# project_buran_schematic.net
KiCad netlist of a schematic drawn in Altium Designer
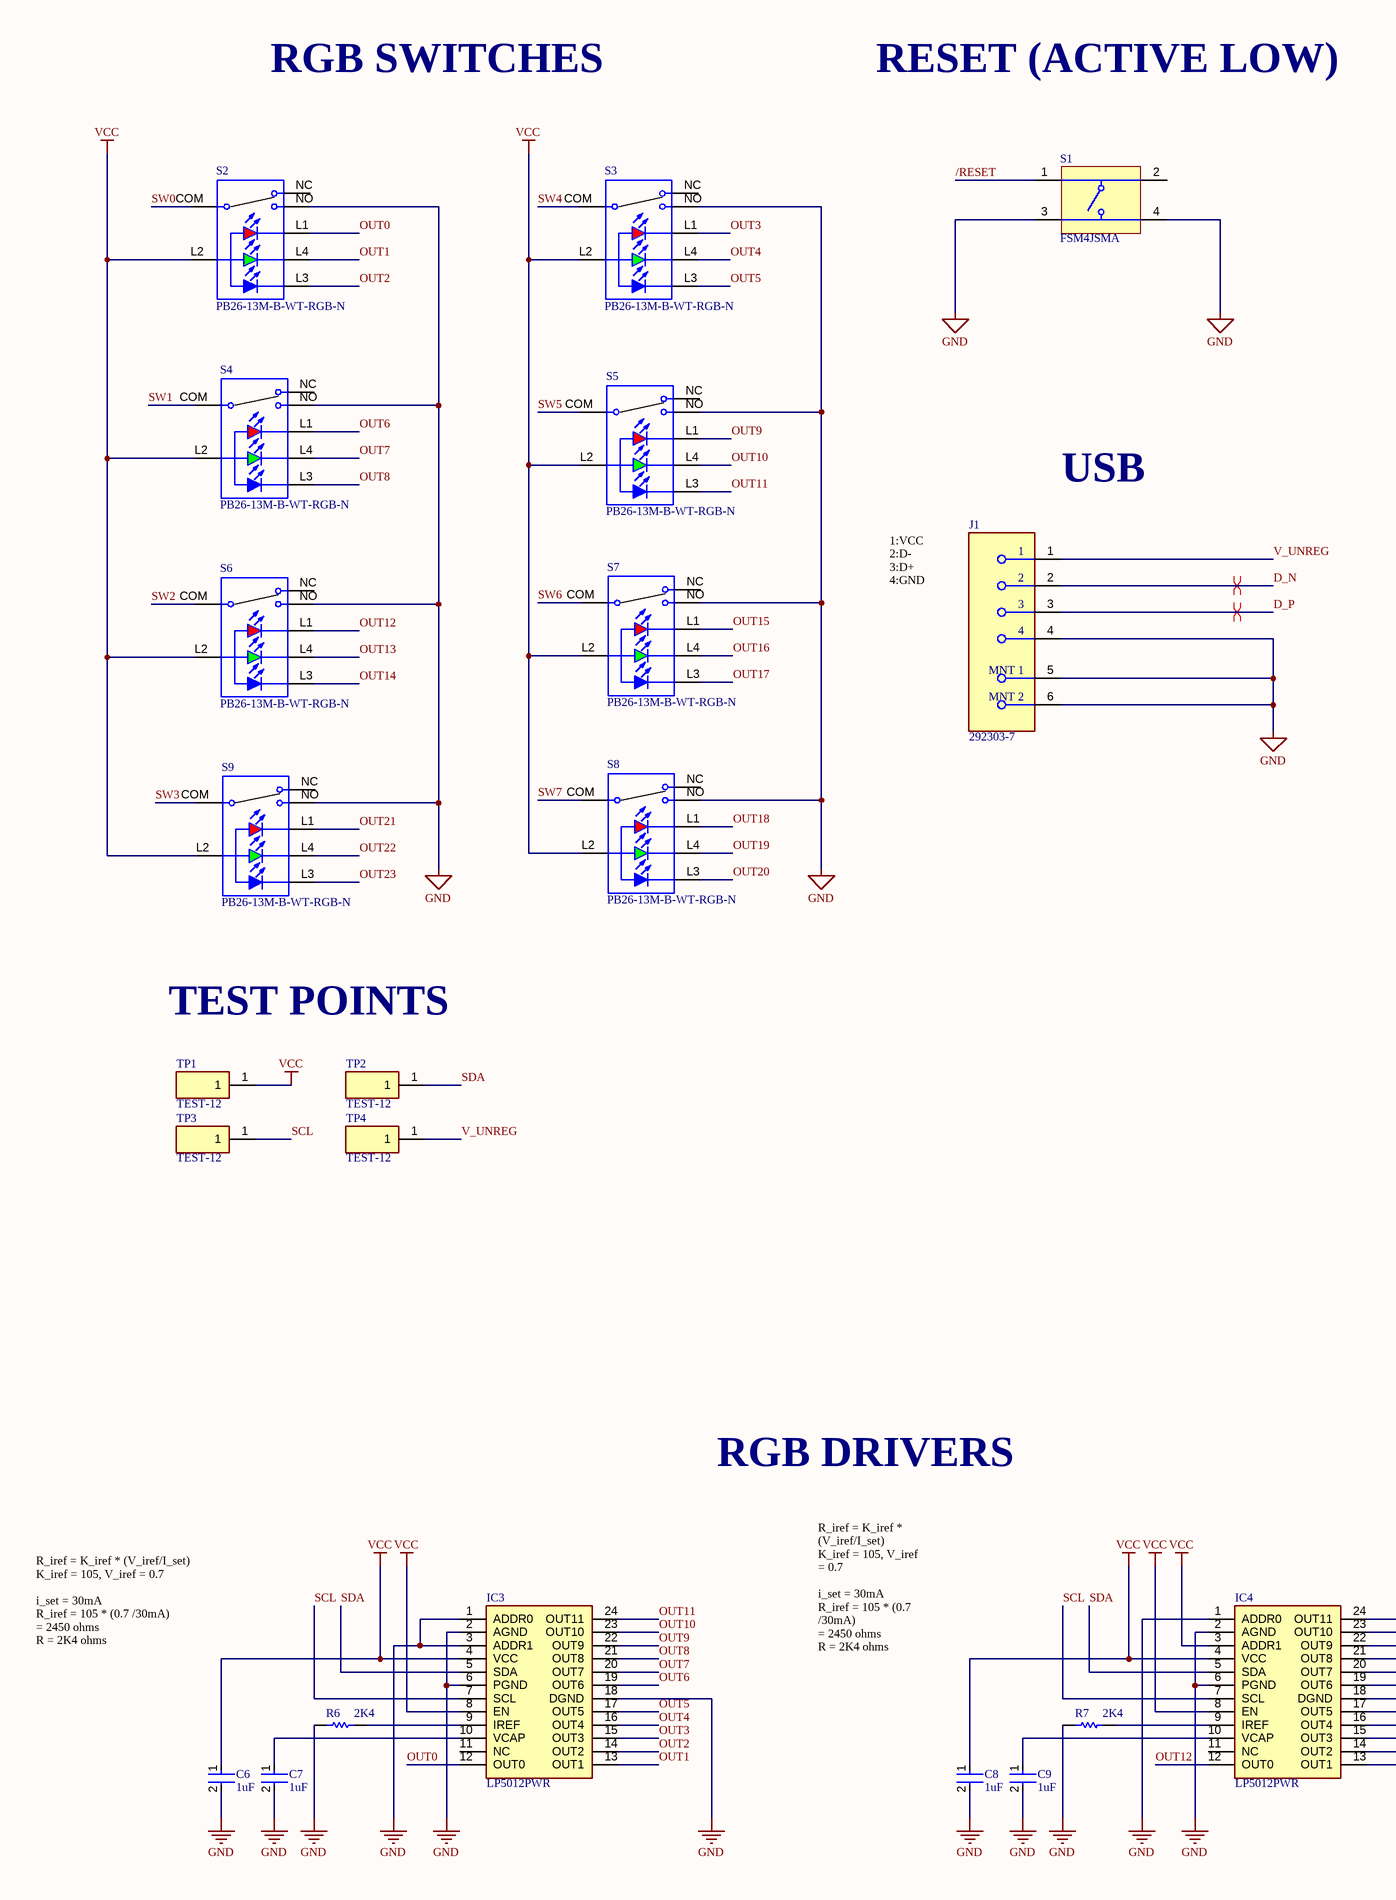
[diagram p0: project_buran_schematic.SchDoc, left]
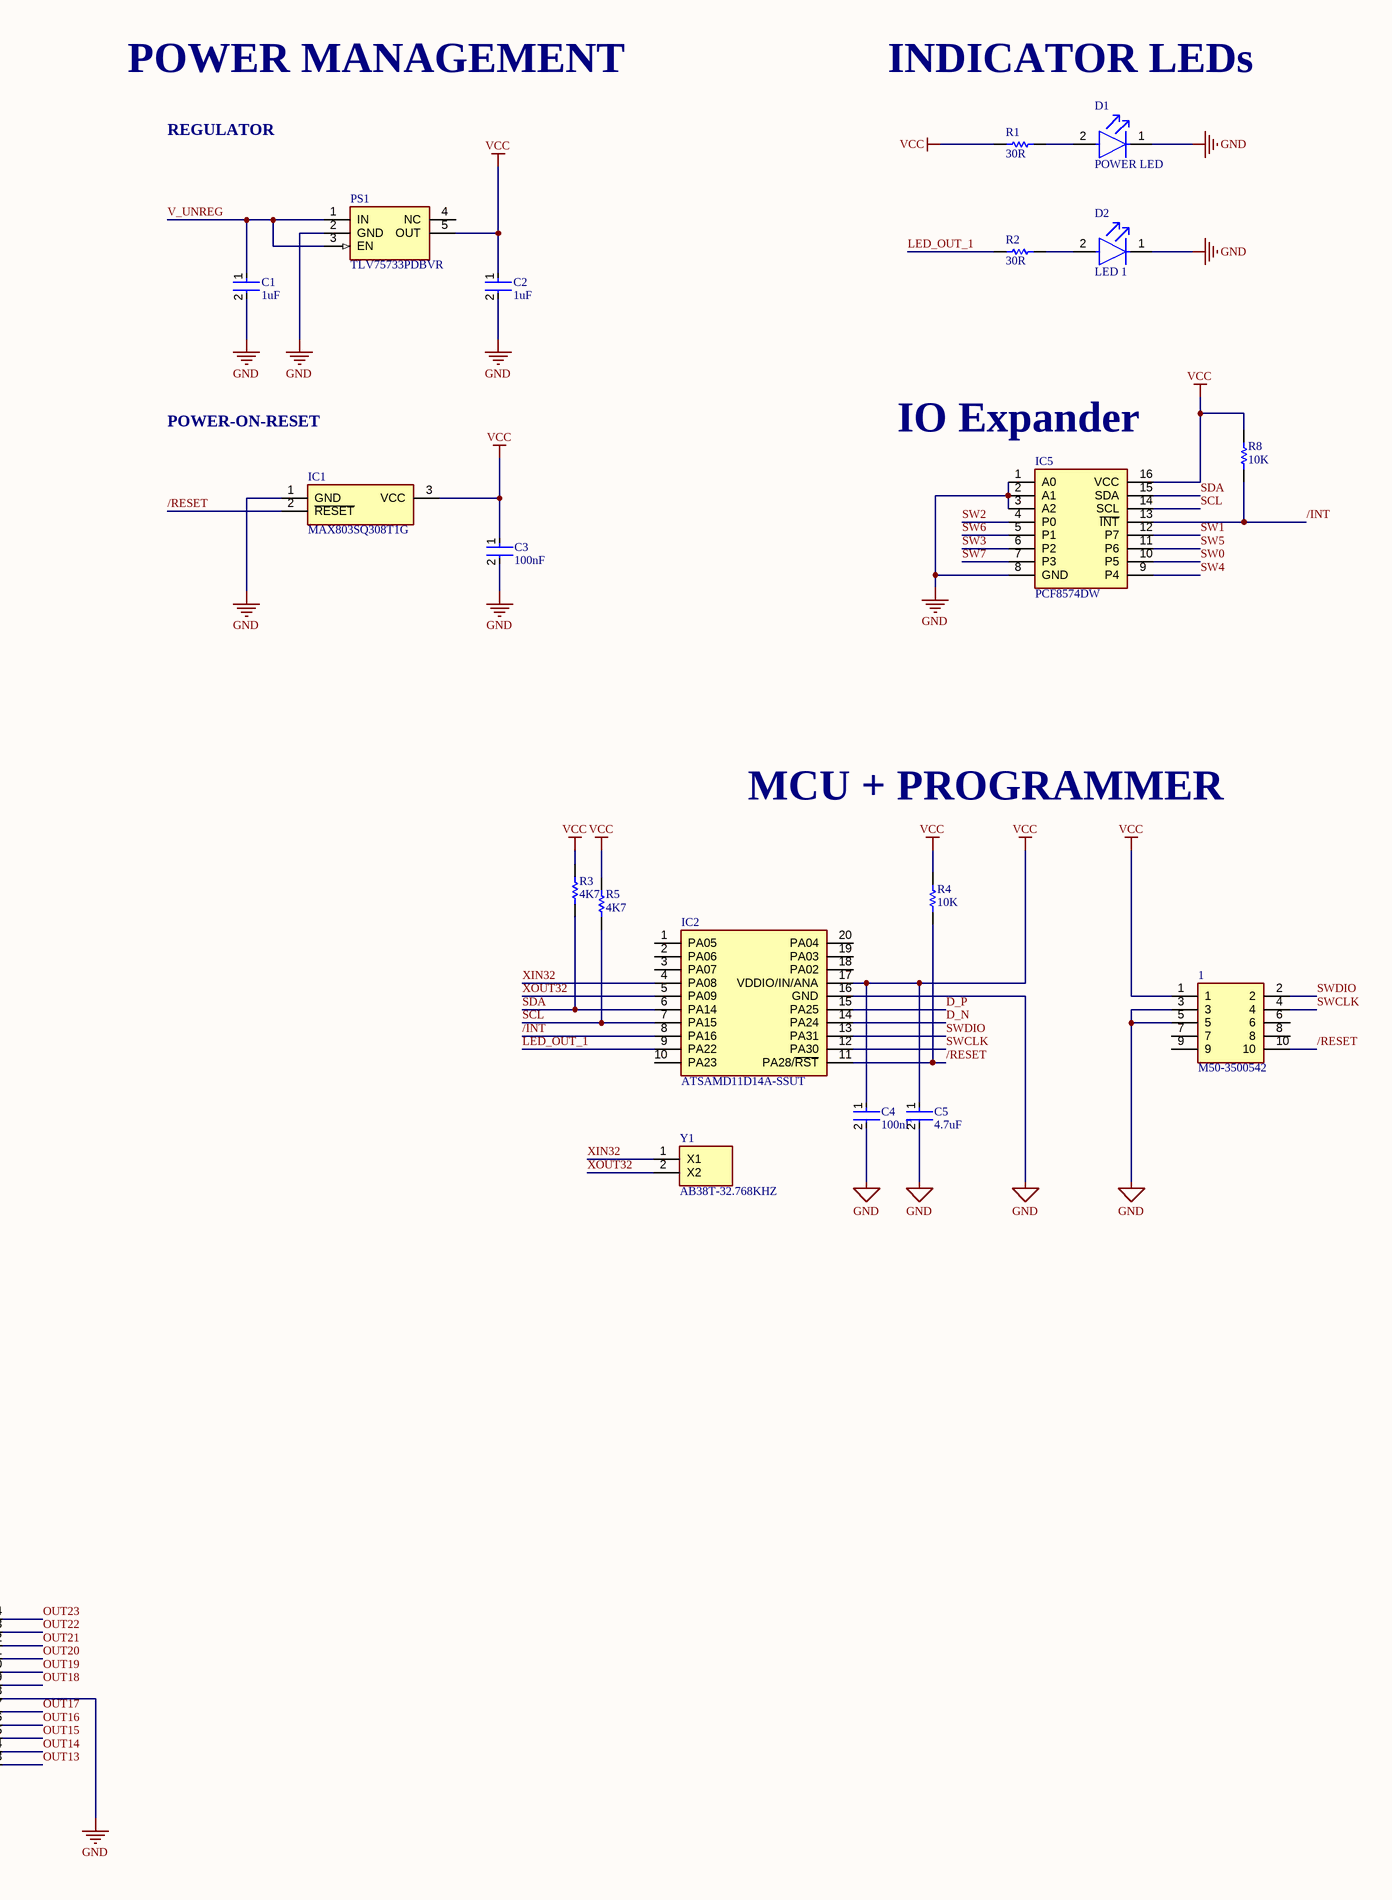
[diagram p1: project_buran_schematic.SchDoc, right]

(export (version "E")
  (design (tool "Eeschema 10.0.6"))
  (components
    (comp (ref "1")
      (value "M50-3500542")
      (footprint "SamacSys:M503500542")
      (description "Connector")
      (fields (field (name "MOUSER PART NUMBER") "855-M50-3500542"))
      (libsource (lib "*") (part "M50-3500542"))
    )
    (comp (ref "C1")
      (value "1uF")
      (footprint "FP-GRM188-0_1-e0_2_0_55-IPC_A")
      (description "Chip Multilayer Ceramic Capacitors for General Purpose, 0603, 10uF, X5R, 15%, 20%, 6.3V")
      (fields (field (name "VOLTAGE") "6.3V") (field (name "TOLERANCE") "20%"))
      (libsource (lib "Altium Content Vault") (part "02cd4be3c70576c341d710602a673aa"))
    )
    (comp (ref "C2")
      (value "1uF")
      (footprint "FP-GRM188-0_1-e0_2_0_55-IPC_A")
      (description "Chip Multilayer Ceramic Capacitors for General Purpose, 0603, 10uF, X5R, 15%, 20%, 6.3V")
      (fields (field (name "VOLTAGE") "6.3V") (field (name "TOLERANCE") "20%"))
      (libsource (lib "Altium Content Vault") (part "02cd4be3c70576c341d710602a673aa"))
    )
    (comp (ref "C3")
      (value "100nF")
      (footprint "FP-GRM188-0_1-e0_2_0_55-IPC_A")
      (description "Chip Multilayer Ceramic Capacitors for General Purpose, 0603, 10uF, X5R, 15%, 20%, 6.3V")
      (fields (field (name "VOLTAGE") "6.3V") (field (name "TOLERANCE") "20%"))
      (libsource (lib "Altium Content Vault") (part "02cd4be3c70576c341d710602a673aa"))
    )
    (comp (ref "C4")
      (value "100nF")
      (footprint "FP-GRM188-0_1-e0_2_0_55-IPC_A")
      (description "Chip Multilayer Ceramic Capacitors for General Purpose, 0603, 10uF, X5R, 15%, 20%, 6.3V")
      (fields (field (name "VOLTAGE") "6.3V") (field (name "TOLERANCE") "20%"))
      (libsource (lib "Altium Content Vault") (part "02cd4be3c70576c341d710602a673aa"))
    )
    (comp (ref "C5")
      (value "4.7uF")
      (footprint "FP-GRM188-0_1-e0_2_0_55-IPC_A")
      (description "Chip Multilayer Ceramic Capacitors for General Purpose, 0603, 10uF, X5R, 15%, 20%, 6.3V")
      (fields (field (name "VOLTAGE") "6.3V") (field (name "TOLERANCE") "20%"))
      (libsource (lib "Altium Content Vault") (part "02cd4be3c70576c341d710602a673aa"))
    )
    (comp (ref "C6")
      (value "1uF")
      (footprint "FP-GRM188-0_1-e0_2_0_55-IPC_A")
      (description "Chip Multilayer Ceramic Capacitors for General Purpose, 0603, 10uF, X5R, 15%, 20%, 6.3V")
      (fields (field (name "VOLTAGE") "6.3V") (field (name "TOLERANCE") "20%"))
      (libsource (lib "Altium Content Vault") (part "02cd4be3c70576c341d710602a673aa"))
    )
    (comp (ref "C7")
      (value "1uF")
      (footprint "FP-GRM188-0_1-e0_2_0_55-IPC_A")
      (description "Chip Multilayer Ceramic Capacitors for General Purpose, 0603, 10uF, X5R, 15%, 20%, 6.3V")
      (fields (field (name "VOLTAGE") "6.3V") (field (name "TOLERANCE") "20%"))
      (libsource (lib "Altium Content Vault") (part "02cd4be3c70576c341d710602a673aa"))
    )
    (comp (ref "C8")
      (value "1uF")
      (footprint "FP-GRM188-0_1-e0_2_0_55-IPC_A")
      (description "Chip Multilayer Ceramic Capacitors for General Purpose, 0603, 10uF, X5R, 15%, 20%, 6.3V")
      (fields (field (name "VOLTAGE") "6.3V") (field (name "TOLERANCE") "20%"))
      (libsource (lib "Altium Content Vault") (part "02cd4be3c70576c341d710602a673aa"))
    )
    (comp (ref "C9")
      (value "1uF")
      (footprint "FP-GRM188-0_1-e0_2_0_55-IPC_A")
      (description "Chip Multilayer Ceramic Capacitors for General Purpose, 0603, 10uF, X5R, 15%, 20%, 6.3V")
      (fields (field (name "VOLTAGE") "6.3V") (field (name "TOLERANCE") "20%"))
      (libsource (lib "Altium Content Vault") (part "02cd4be3c70576c341d710602a673aa"))
    )
    (comp (ref "D1")
      (value "POWER LED")
      (footprint "FP-LTST-C190GKT-MFG")
      (description "LED GREEN CLEAR CHIP SMD")
      (fields (field (name "VOLTAGE") "2V"))
      (libsource (lib "Altium Content Vault") (part "8706943c75ba83719d021d2fdc84c58"))
    )
    (comp (ref "D2")
      (value "LED 1")
      (footprint "FP-LTST-C190GKT-MFG")
      (description "LED GREEN CLEAR CHIP SMD")
      (fields (field (name "VOLTAGE") "2V"))
      (libsource (lib "Altium Content Vault") (part "8706943c75ba83719d021d2fdc84c58"))
    )
    (comp (ref "IC1")
      (value "MAX803SQ308T1G")
      (footprint "SamacSys:SOT65P220X100-3N")
      (description "Integrated Circuit")
      (fields (field (name "MOUSER PART NUMBER") "863-MAX803SQ308T1G"))
      (libsource (lib "SamacSys") (part "MAX803SQ308T1G"))
    )
    (comp (ref "IC2")
      (value "ATSAMD11D14A-SSUT")
      (footprint "SOIC127P1032X265-20N")
      (description "Integrated Circuit")
      (fields (field (name "MOUSER PART NUMBER") "556-ATSAMD11D14ASSUT"))
      (libsource (lib "SamacSys") (part "ATSAMD11D14A-SSUT"))
    )
    (comp (ref "IC3")
      (value "LP5012PWR")
      (footprint "SOP65P640X120-24N")
      (description "Integrated Circuit")
      (fields (field (name "MOUSER PART NUMBER") "595-LP5012PWR"))
      (libsource (lib "*") (part "LP5012PWR"))
    )
    (comp (ref "IC4")
      (value "LP5012PWR")
      (footprint "SOP65P640X120-24N")
      (description "Integrated Circuit")
      (fields (field (name "MOUSER PART NUMBER") "595-LP5012PWR"))
      (libsource (lib "*") (part "LP5012PWR"))
    )
    (comp (ref "IC5")
      (value "PCF8574DW")
      (footprint "SamacSys:SOIC127P1030X265-16N")
      (description "Integrated Circuit")
      (fields (field (name "MOUSER PART NUMBER") "595-PCF8574DW"))
      (libsource (lib "*") (part "PCF8574DW"))
    )
    (comp (ref "J1")
      (value "292303-7")
      (footprint "FP-292303-7-MFG")
      (description "CONN RCPT USB2.0 TYPEA 4P SMD RA")
      (fields
        (field (name "OCTOPART") "https://octopart.com/292303-7-te+connectivity-42840369")
        (field (name "MANUFACTURER") "TE Connectivity")
      )
      (libsource (lib "Altium Content Vault") (part "79e6714efa0bb2f851c24b2688127c9"))
    )
    (comp (ref "PS1")
      (value "TLV75733PDBVR")
      (footprint "SamacSys:SOT95P280X145-5N")
      (description "Power Supply")
      (fields (field (name "MOUSER PART NUMBER") "595-TLV75733PDBVR"))
      (libsource (lib "SamacSys") (part "TLV75733PDBVR"))
    )
    (comp (ref "R1")
      (value "30R")
      (footprint "RESC1609X50X30NL10T20")
      (fields (field (name "PART NUMBER") "CRCW0603110RFKEA") (field (name "MANUFACTURER") "Vishay Dale"))
      (libsource (lib "Altium Content Vault") (part "RES"))
    )
    (comp (ref "R2")
      (value "30R")
      (footprint "RESC1609X50X30NL10T20")
      (fields (field (name "PART NUMBER") "CRCW0603110RFKEA") (field (name "MANUFACTURER") "Vishay Dale"))
      (libsource (lib "Altium Content Vault") (part "RES"))
    )
    (comp (ref "R3")
      (value "4K7")
      (footprint "RESC1609X50X30NL10T20")
      (fields (field (name "PART NUMBER") "CRCW0603110RFKEA") (field (name "MANUFACTURER") "Vishay Dale"))
      (libsource (lib "Altium Content Vault") (part "RES"))
    )
    (comp (ref "R4")
      (value "10K")
      (footprint "RESC1609X50X30NL10T20")
      (fields (field (name "PART NUMBER") "CRCW0603110RFKEA") (field (name "MANUFACTURER") "Vishay Dale"))
      (libsource (lib "Altium Content Vault") (part "RES"))
    )
    (comp (ref "R5")
      (value "4K7")
      (footprint "RESC1609X50X30NL10T20")
      (fields (field (name "PART NUMBER") "CRCW0603110RFKEA") (field (name "MANUFACTURER") "Vishay Dale"))
      (libsource (lib "Altium Content Vault") (part "RES"))
    )
    (comp (ref "R6")
      (value "2K4")
      (footprint "RESC1609X50X30NL10T20")
      (fields (field (name "PART NUMBER") "CRCW0603110RFKEA") (field (name "MANUFACTURER") "Vishay Dale"))
      (libsource (lib "Altium Content Vault") (part "RES"))
    )
    (comp (ref "R7")
      (value "2K4")
      (footprint "RESC1609X50X30NL10T20")
      (fields (field (name "PART NUMBER") "CRCW0603110RFKEA") (field (name "MANUFACTURER") "Vishay Dale"))
      (libsource (lib "Altium Content Vault") (part "RES"))
    )
    (comp (ref "R8")
      (value "10K")
      (footprint "RESC1609X50X30NL10T20")
      (fields (field (name "PART NUMBER") "CRCW0603110RFKEA") (field (name "MANUFACTURER") "Vishay Dale"))
      (libsource (lib "Altium Content Vault") (part "RES"))
    )
    (comp (ref "S1")
      (value "FSM4JSMA")
      (footprint "TECO-FSM4JSMA_V")
      (description "Swicth, SPST, 24 V, -35 to 85 degC, 4-Pin SMD, RoHS, Tape and Reel")
      (fields (field (name "MANUFACTURER") "TE Connectivity"))
      (libsource (lib "Altium Content Vault") (part "SW-SPST-4_A"))
    )
    (comp (ref "S2")
      (value "PB26-13M-B-WT-RGB-N")
      (footprint "PCBComponent_1 - duplicate")
      (description "WS-PBTL Illuminated THT Push Button Switch, Red & Green & Blue")
      (fields (field (name "PART NUMBER") "465M111172501") (field (name "PUBLISHER") "Wurth Elektronik"))
      (libsource (lib "BuranComponent") (part "PB26-13M-B-WT-RGB-N"))
    )
    (comp (ref "S3")
      (value "PB26-13M-B-WT-RGB-N")
      (footprint "PCBComponent_1 - duplicate")
      (description "WS-PBTL Illuminated THT Push Button Switch, Red & Green & Blue")
      (fields (field (name "PART NUMBER") "465M111172501") (field (name "PUBLISHER") "Wurth Elektronik"))
      (libsource (lib "BuranComponent") (part "PB26-13M-B-WT-RGB-N"))
    )
    (comp (ref "S4")
      (value "PB26-13M-B-WT-RGB-N")
      (footprint "PCBComponent_1 - duplicate")
      (description "WS-PBTL Illuminated THT Push Button Switch, Red & Green & Blue")
      (fields (field (name "PART NUMBER") "465M111172501") (field (name "PUBLISHER") "Wurth Elektronik"))
      (libsource (lib "BuranComponent") (part "PB26-13M-B-WT-RGB-N"))
    )
    (comp (ref "S5")
      (value "PB26-13M-B-WT-RGB-N")
      (footprint "PCBComponent_1 - duplicate")
      (description "WS-PBTL Illuminated THT Push Button Switch, Red & Green & Blue")
      (fields (field (name "PART NUMBER") "465M111172501") (field (name "PUBLISHER") "Wurth Elektronik"))
      (libsource (lib "BuranComponent") (part "PB26-13M-B-WT-RGB-N"))
    )
    (comp (ref "S6")
      (value "PB26-13M-B-WT-RGB-N")
      (footprint "PCBComponent_1 - duplicate")
      (description "WS-PBTL Illuminated THT Push Button Switch, Red & Green & Blue")
      (fields (field (name "PART NUMBER") "465M111172501") (field (name "PUBLISHER") "Wurth Elektronik"))
      (libsource (lib "BuranComponent") (part "PB26-13M-B-WT-RGB-N"))
    )
    (comp (ref "S7")
      (value "PB26-13M-B-WT-RGB-N")
      (footprint "PCBComponent_1 - duplicate")
      (description "WS-PBTL Illuminated THT Push Button Switch, Red & Green & Blue")
      (fields (field (name "PART NUMBER") "465M111172501") (field (name "PUBLISHER") "Wurth Elektronik"))
      (libsource (lib "BuranComponent") (part "PB26-13M-B-WT-RGB-N"))
    )
    (comp (ref "S8")
      (value "PB26-13M-B-WT-RGB-N")
      (footprint "PCBComponent_1 - duplicate")
      (description "WS-PBTL Illuminated THT Push Button Switch, Red & Green & Blue")
      (fields (field (name "PART NUMBER") "465M111172501") (field (name "PUBLISHER") "Wurth Elektronik"))
      (libsource (lib "BuranComponent") (part "PB26-13M-B-WT-RGB-N"))
    )
    (comp (ref "S9")
      (value "PB26-13M-B-WT-RGB-N")
      (footprint "PCBComponent_1 - duplicate")
      (description "WS-PBTL Illuminated THT Push Button Switch, Red & Green & Blue")
      (fields (field (name "PART NUMBER") "465M111172501") (field (name "PUBLISHER") "Wurth Elektronik"))
      (libsource (lib "BuranComponent") (part "PB26-13M-B-WT-RGB-N"))
    )
    (comp (ref "TP1")
      (value "TEST-12")
      (footprint "SamacSys:TEST12")
      (description "Test Point")
      (libsource (lib "*") (part "TEST-12"))
    )
    (comp (ref "TP2")
      (value "TEST-12")
      (footprint "SamacSys:TEST12")
      (description "Test Point")
      (libsource (lib "*") (part "TEST-12"))
    )
    (comp (ref "TP3")
      (value "TEST-12")
      (footprint "SamacSys:TEST12")
      (description "Test Point")
      (libsource (lib "*") (part "TEST-12"))
    )
    (comp (ref "TP4")
      (value "TEST-12")
      (footprint "SamacSys:TEST12")
      (description "Test Point")
      (libsource (lib "*") (part "TEST-12"))
    )
    (comp (ref "Y1")
      (value "AB38T-32.768KHZ")
      (footprint "AB38T32768KHZ")
      (description "Crystal or Oscillator")
      (fields (field (name "MOUSER PART NUMBER") "815-AB38T-32.768KHZ"))
      (libsource (lib "SamacSys") (part "AB38T-32.768KHZ"))
    )
  )
  (nets
    (net (code "1") (name "/D_N") (class "Default")
      (node (ref "IC2") (pin "14") (pinfunction "PA24_14") (pintype "passive"))
      (node (ref "J1") (pin "2") (pinfunction "2_2") (pintype "passive"))
    )
    (net (code "2") (name "/D_P") (class "Default")
      (node (ref "IC2") (pin "15") (pinfunction "PA25_15") (pintype "passive"))
      (node (ref "J1") (pin "3") (pinfunction "3_3") (pintype "passive"))
    )
    (net (code "3") (name "/LED_OUT_1") (class "Default")
      (node (ref "IC2") (pin "9") (pinfunction "PA22_9") (pintype "passive"))
      (node (ref "R2") (pin "2") (pinfunction "2_2") (pintype "passive"))
    )
    (net (code "4") (name "/OUT0") (class "Default")
      (node (ref "IC3") (pin "12") (pinfunction "OUT0_12") (pintype "passive"))
      (node (ref "S2") (pin "L1") (pinfunction "L4_L1") (pintype "passive"))
    )
    (net (code "5") (name "/OUT1") (class "Default")
      (node (ref "IC3") (pin "13") (pinfunction "OUT1_13") (pintype "passive"))
      (node (ref "S2") (pin "L4") (pinfunction "L4_L4") (pintype "passive"))
    )
    (net (code "6") (name "/OUT2") (class "Default")
      (node (ref "IC3") (pin "14") (pinfunction "OUT2_14") (pintype "passive"))
      (node (ref "S2") (pin "L3") (pinfunction "L2_L3") (pintype "passive"))
    )
    (net (code "7") (name "/OUT3") (class "Default")
      (node (ref "IC3") (pin "15") (pinfunction "OUT3_15") (pintype "passive"))
      (node (ref "S3") (pin "L1") (pinfunction "L4_L1") (pintype "passive"))
    )
    (net (code "8") (name "/OUT4") (class "Default")
      (node (ref "IC3") (pin "16") (pinfunction "OUT4_16") (pintype "passive"))
      (node (ref "S3") (pin "L4") (pinfunction "L4_L4") (pintype "passive"))
    )
    (net (code "9") (name "/OUT5") (class "Default")
      (node (ref "IC3") (pin "17") (pinfunction "OUT5_17") (pintype "passive"))
      (node (ref "S3") (pin "L3") (pinfunction "L2_L3") (pintype "passive"))
    )
    (net (code "10") (name "/OUT6") (class "Default")
      (node (ref "IC3") (pin "19") (pinfunction "OUT6_19") (pintype "passive"))
      (node (ref "S4") (pin "L1") (pinfunction "L4_L1") (pintype "passive"))
    )
    (net (code "11") (name "/OUT7") (class "Default")
      (node (ref "IC3") (pin "20") (pinfunction "OUT7_20") (pintype "passive"))
      (node (ref "S4") (pin "L4") (pinfunction "L4_L4") (pintype "passive"))
    )
    (net (code "12") (name "/OUT8") (class "Default")
      (node (ref "IC3") (pin "21") (pinfunction "OUT8_21") (pintype "passive"))
      (node (ref "S4") (pin "L3") (pinfunction "L2_L3") (pintype "passive"))
    )
    (net (code "13") (name "/OUT9") (class "Default")
      (node (ref "IC3") (pin "22") (pinfunction "OUT9_22") (pintype "passive"))
      (node (ref "S5") (pin "L1") (pinfunction "L4_L1") (pintype "passive"))
    )
    (net (code "14") (name "/OUT10") (class "Default")
      (node (ref "IC3") (pin "23") (pinfunction "OUT10_23") (pintype "passive"))
      (node (ref "S5") (pin "L4") (pinfunction "L4_L4") (pintype "passive"))
    )
    (net (code "15") (name "/OUT11") (class "Default")
      (node (ref "IC3") (pin "24") (pinfunction "OUT11_24") (pintype "passive"))
      (node (ref "S5") (pin "L3") (pinfunction "L2_L3") (pintype "passive"))
    )
    (net (code "16") (name "/OUT12") (class "Default")
      (node (ref "IC4") (pin "12") (pinfunction "OUT0_12") (pintype "passive"))
      (node (ref "S6") (pin "L1") (pinfunction "L4_L1") (pintype "passive"))
    )
    (net (code "17") (name "/OUT13") (class "Default")
      (node (ref "IC4") (pin "13") (pinfunction "OUT1_13") (pintype "passive"))
      (node (ref "S6") (pin "L4") (pinfunction "L4_L4") (pintype "passive"))
    )
    (net (code "18") (name "/OUT14") (class "Default")
      (node (ref "IC4") (pin "14") (pinfunction "OUT2_14") (pintype "passive"))
      (node (ref "S6") (pin "L3") (pinfunction "L2_L3") (pintype "passive"))
    )
    (net (code "19") (name "/OUT15") (class "Default")
      (node (ref "IC4") (pin "15") (pinfunction "OUT3_15") (pintype "passive"))
      (node (ref "S7") (pin "L1") (pinfunction "L4_L1") (pintype "passive"))
    )
    (net (code "20") (name "/OUT16") (class "Default")
      (node (ref "IC4") (pin "16") (pinfunction "OUT4_16") (pintype "passive"))
      (node (ref "S7") (pin "L4") (pinfunction "L4_L4") (pintype "passive"))
    )
    (net (code "21") (name "/OUT17") (class "Default")
      (node (ref "IC4") (pin "17") (pinfunction "OUT5_17") (pintype "passive"))
      (node (ref "S7") (pin "L3") (pinfunction "L2_L3") (pintype "passive"))
    )
    (net (code "22") (name "/OUT18") (class "Default")
      (node (ref "IC4") (pin "19") (pinfunction "OUT6_19") (pintype "passive"))
      (node (ref "S8") (pin "L1") (pinfunction "L4_L1") (pintype "passive"))
    )
    (net (code "23") (name "/OUT19") (class "Default")
      (node (ref "IC4") (pin "20") (pinfunction "OUT7_20") (pintype "passive"))
      (node (ref "S8") (pin "L4") (pinfunction "L4_L4") (pintype "passive"))
    )
    (net (code "24") (name "/OUT20") (class "Default")
      (node (ref "IC4") (pin "21") (pinfunction "OUT8_21") (pintype "passive"))
      (node (ref "S8") (pin "L3") (pinfunction "L2_L3") (pintype "passive"))
    )
    (net (code "25") (name "/OUT21") (class "Default")
      (node (ref "IC4") (pin "22") (pinfunction "OUT9_22") (pintype "passive"))
      (node (ref "S9") (pin "L1") (pinfunction "L4_L1") (pintype "passive"))
    )
    (net (code "26") (name "/OUT22") (class "Default")
      (node (ref "IC4") (pin "23") (pinfunction "OUT10_23") (pintype "passive"))
      (node (ref "S9") (pin "L4") (pinfunction "L4_L4") (pintype "passive"))
    )
    (net (code "27") (name "/OUT23") (class "Default")
      (node (ref "IC4") (pin "24") (pinfunction "OUT11_24") (pintype "passive"))
      (node (ref "S9") (pin "L3") (pinfunction "L2_L3") (pintype "passive"))
    )
    (net (code "28") (name "/SCL") (class "Default")
      (node (ref "IC2") (pin "7") (pinfunction "PA15_7") (pintype "passive"))
      (node (ref "IC3") (pin "7") (pinfunction "SCL_7") (pintype "passive"))
      (node (ref "IC4") (pin "7") (pinfunction "SCL_7") (pintype "passive"))
      (node (ref "IC5") (pin "14") (pinfunction "SCL_14") (pintype "passive"))
      (node (ref "R5") (pin "1") (pinfunction "1_1") (pintype "passive"))
      (node (ref "TP3") (pin "1") (pinfunction "1_1") (pintype "passive"))
    )
    (net (code "29") (name "/SDA") (class "Default")
      (node (ref "IC2") (pin "6") (pinfunction "PA14_6") (pintype "passive"))
      (node (ref "IC3") (pin "5") (pinfunction "SDA_5") (pintype "passive"))
      (node (ref "IC4") (pin "5") (pinfunction "SDA_5") (pintype "passive"))
      (node (ref "IC5") (pin "15") (pinfunction "SDA_15") (pintype "passive"))
      (node (ref "R3") (pin "1") (pinfunction "1_1") (pintype "passive"))
      (node (ref "TP2") (pin "1") (pinfunction "1_1") (pintype "passive"))
    )
    (net (code "30") (name "/SW0") (class "Default")
      (node (ref "IC5") (pin "10") (pinfunction "P5_10") (pintype "passive"))
      (node (ref "S2") (pin "COM") (pinfunction "COM_COM") (pintype "passive"))
    )
    (net (code "31") (name "/SW1") (class "Default")
      (node (ref "IC5") (pin "12") (pinfunction "P7_12") (pintype "passive"))
      (node (ref "S4") (pin "COM") (pinfunction "COM_COM") (pintype "passive"))
    )
    (net (code "32") (name "/SW2") (class "Default")
      (node (ref "IC5") (pin "4") (pinfunction "P0_4") (pintype "passive"))
      (node (ref "S6") (pin "COM") (pinfunction "COM_COM") (pintype "passive"))
    )
    (net (code "33") (name "/SW3") (class "Default")
      (node (ref "IC5") (pin "6") (pinfunction "P2_6") (pintype "passive"))
      (node (ref "S9") (pin "COM") (pinfunction "COM_COM") (pintype "passive"))
    )
    (net (code "34") (name "/SW4") (class "Default")
      (node (ref "IC5") (pin "9") (pinfunction "P4_9") (pintype "passive"))
      (node (ref "S3") (pin "COM") (pinfunction "COM_COM") (pintype "passive"))
    )
    (net (code "35") (name "/SW5") (class "Default")
      (node (ref "IC5") (pin "11") (pinfunction "P6_11") (pintype "passive"))
      (node (ref "S5") (pin "COM") (pinfunction "COM_COM") (pintype "passive"))
    )
    (net (code "36") (name "/SW6") (class "Default")
      (node (ref "IC5") (pin "5") (pinfunction "P1_5") (pintype "passive"))
      (node (ref "S7") (pin "COM") (pinfunction "COM_COM") (pintype "passive"))
    )
    (net (code "37") (name "/SW7") (class "Default")
      (node (ref "IC5") (pin "7") (pinfunction "P3_7") (pintype "passive"))
      (node (ref "S8") (pin "COM") (pinfunction "COM_COM") (pintype "passive"))
    )
    (net (code "38") (name "/SWCLK") (class "Default")
      (node (ref "1") (pin "4") (pinfunction "4_4") (pintype "passive"))
      (node (ref "IC2") (pin "12") (pinfunction "PA30_12") (pintype "passive"))
    )
    (net (code "39") (name "/SWDIO") (class "Default")
      (node (ref "1") (pin "2") (pinfunction "2_2") (pintype "passive"))
      (node (ref "IC2") (pin "13") (pinfunction "PA31_13") (pintype "passive"))
    )
    (net (code "40") (name "/V_UNREG") (class "Default")
      (node (ref "C1") (pin "1") (pinfunction "1_1") (pintype "passive"))
      (node (ref "J1") (pin "1") (pinfunction "1_1") (pintype "passive"))
      (node (ref "PS1") (pin "1") (pinfunction "IN_1") (pintype "power_in"))
      (node (ref "PS1") (pin "3") (pinfunction "EN_3") (pintype "input"))
      (node (ref "TP4") (pin "1") (pinfunction "1_1") (pintype "passive"))
    )
    (net (code "41") (name "/XIN32") (class "Default")
      (node (ref "IC2") (pin "4") (pinfunction "PA08_4") (pintype "passive"))
      (node (ref "Y1") (pin "1") (pinfunction "X1_1") (pintype "passive"))
    )
    (net (code "42") (name "/XOUT32") (class "Default")
      (node (ref "IC2") (pin "5") (pinfunction "PA09_5") (pintype "passive"))
      (node (ref "Y1") (pin "2") (pinfunction "X2_2") (pintype "passive"))
    )
    (net (code "43") (name "/{slash}INT") (class "Default")
      (node (ref "IC2") (pin "8") (pinfunction "PA16_8") (pintype "passive"))
      (node (ref "IC5") (pin "13") (pinfunction "~{INT}_13") (pintype "passive"))
      (node (ref "R8") (pin "1") (pinfunction "1_1") (pintype "passive"))
    )
    (net (code "44") (name "/{slash}RESET") (class "Default")
      (node (ref "1") (pin "10") (pinfunction "10_10") (pintype "passive"))
      (node (ref "IC1") (pin "2") (pinfunction "~{RESET}_2") (pintype "passive"))
      (node (ref "IC2") (pin "11") (pinfunction "PA28/~{RST}_11") (pintype "passive"))
      (node (ref "R4") (pin "1") (pinfunction "1_1") (pintype "passive"))
      (node (ref "S1") (pin "1") (pinfunction "1_1") (pintype "passive"))
    )
    (net (code "45") (name "GND") (class "Default")
      (node (ref "1") (pin "3") (pinfunction "3_3") (pintype "passive"))
      (node (ref "1") (pin "5") (pinfunction "5_5") (pintype "passive"))
      (node (ref "C1") (pin "2") (pinfunction "2_2") (pintype "passive"))
      (node (ref "C2") (pin "2") (pinfunction "2_2") (pintype "passive"))
      (node (ref "C3") (pin "2") (pinfunction "2_2") (pintype "passive"))
      (node (ref "C4") (pin "2") (pinfunction "2_2") (pintype "passive"))
      (node (ref "C5") (pin "2") (pinfunction "2_2") (pintype "passive"))
      (node (ref "C6") (pin "2") (pinfunction "2_2") (pintype "passive"))
      (node (ref "C7") (pin "2") (pinfunction "2_2") (pintype "passive"))
      (node (ref "C8") (pin "2") (pinfunction "2_2") (pintype "passive"))
      (node (ref "C9") (pin "2") (pinfunction "2_2") (pintype "passive"))
      (node (ref "D1") (pin "1") (pinfunction "C_1") (pintype "passive"))
      (node (ref "D2") (pin "1") (pinfunction "C_1") (pintype "passive"))
      (node (ref "IC1") (pin "1") (pinfunction "GND_1") (pintype "power_in"))
      (node (ref "IC2") (pin "16") (pinfunction "GND_16") (pintype "passive"))
      (node (ref "IC3") (pin "1") (pinfunction "ADDR0_1") (pintype "passive"))
      (node (ref "IC3") (pin "18") (pinfunction "DGND_18") (pintype "passive"))
      (node (ref "IC3") (pin "2") (pinfunction "AGND_2") (pintype "passive"))
      (node (ref "IC3") (pin "3") (pinfunction "ADDR1_3") (pintype "passive"))
      (node (ref "IC3") (pin "6") (pinfunction "PGND_6") (pintype "passive"))
      (node (ref "IC4") (pin "1") (pinfunction "ADDR0_1") (pintype "passive"))
      (node (ref "IC4") (pin "18") (pinfunction "DGND_18") (pintype "passive"))
      (node (ref "IC4") (pin "2") (pinfunction "AGND_2") (pintype "passive"))
      (node (ref "IC4") (pin "6") (pinfunction "PGND_6") (pintype "passive"))
      (node (ref "IC5") (pin "1") (pinfunction "A0_1") (pintype "passive"))
      (node (ref "IC5") (pin "2") (pinfunction "A1_2") (pintype "passive"))
      (node (ref "IC5") (pin "3") (pinfunction "A2_3") (pintype "passive"))
      (node (ref "IC5") (pin "8") (pinfunction "GND_8") (pintype "passive"))
      (node (ref "J1") (pin "4") (pinfunction "4_4") (pintype "passive"))
      (node (ref "J1") (pin "5") (pinfunction "MNT_1_5") (pintype "passive"))
      (node (ref "J1") (pin "6") (pinfunction "MNT_2_6") (pintype "passive"))
      (node (ref "PS1") (pin "2") (pinfunction "GND_2") (pintype "power_in"))
      (node (ref "R6") (pin "1") (pinfunction "1_1") (pintype "passive"))
      (node (ref "R7") (pin "1") (pinfunction "1_1") (pintype "passive"))
      (node (ref "S1") (pin "3") (pinfunction "3_3") (pintype "passive"))
      (node (ref "S1") (pin "4") (pinfunction "4_4") (pintype "passive"))
      (node (ref "S2") (pin "NO") (pinfunction "NO_NO") (pintype "passive"))
      (node (ref "S3") (pin "NO") (pinfunction "NO_NO") (pintype "passive"))
      (node (ref "S4") (pin "NO") (pinfunction "NO_NO") (pintype "passive"))
      (node (ref "S5") (pin "NO") (pinfunction "NO_NO") (pintype "passive"))
      (node (ref "S6") (pin "NO") (pinfunction "NO_NO") (pintype "passive"))
      (node (ref "S7") (pin "NO") (pinfunction "NO_NO") (pintype "passive"))
      (node (ref "S8") (pin "NO") (pinfunction "NO_NO") (pintype "passive"))
      (node (ref "S9") (pin "NO") (pinfunction "NO_NO") (pintype "passive"))
    )
    (net (code "46") (name "Net-(D1-A)") (class "Default")
      (node (ref "D1") (pin "2") (pinfunction "A_2") (pintype "passive"))
      (node (ref "R1") (pin "1") (pinfunction "1_1") (pintype "passive"))
    )
    (net (code "47") (name "Net-(D2-A)") (class "Default")
      (node (ref "D2") (pin "2") (pinfunction "A_2") (pintype "passive"))
      (node (ref "R2") (pin "1") (pinfunction "1_1") (pintype "passive"))
    )
    (net (code "48") (name "Net-(IC3-IREF)") (class "Default")
      (node (ref "IC3") (pin "9") (pinfunction "IREF_9") (pintype "passive"))
      (node (ref "R6") (pin "2") (pinfunction "2_2") (pintype "passive"))
    )
    (net (code "49") (name "Net-(IC3-VCAP)") (class "Default")
      (node (ref "C7") (pin "1") (pinfunction "1_1") (pintype "passive"))
      (node (ref "IC3") (pin "10") (pinfunction "VCAP_10") (pintype "passive"))
    )
    (net (code "50") (name "Net-(IC4-IREF)") (class "Default")
      (node (ref "IC4") (pin "9") (pinfunction "IREF_9") (pintype "passive"))
      (node (ref "R7") (pin "2") (pinfunction "2_2") (pintype "passive"))
    )
    (net (code "51") (name "Net-(IC4-VCAP)") (class "Default")
      (node (ref "C9") (pin "1") (pinfunction "1_1") (pintype "passive"))
      (node (ref "IC4") (pin "10") (pinfunction "VCAP_10") (pintype "passive"))
    )
    (net (code "52") (name "VCC") (class "Default")
      (node (ref "1") (pin "1") (pinfunction "1_1") (pintype "passive"))
      (node (ref "C2") (pin "1") (pinfunction "1_1") (pintype "passive"))
      (node (ref "C3") (pin "1") (pinfunction "1_1") (pintype "passive"))
      (node (ref "C4") (pin "1") (pinfunction "1_1") (pintype "passive"))
      (node (ref "C5") (pin "1") (pinfunction "1_1") (pintype "passive"))
      (node (ref "C6") (pin "1") (pinfunction "1_1") (pintype "passive"))
      (node (ref "C8") (pin "1") (pinfunction "1_1") (pintype "passive"))
      (node (ref "IC1") (pin "3") (pinfunction "VCC_3") (pintype "power_in"))
      (node (ref "IC2") (pin "17") (pinfunction "VDDIO/IN/ANA_17") (pintype "passive"))
      (node (ref "IC3") (pin "4") (pinfunction "VCC_4") (pintype "passive"))
      (node (ref "IC3") (pin "8") (pinfunction "EN_8") (pintype "passive"))
      (node (ref "IC4") (pin "3") (pinfunction "ADDR1_3") (pintype "passive"))
      (node (ref "IC4") (pin "4") (pinfunction "VCC_4") (pintype "passive"))
      (node (ref "IC4") (pin "8") (pinfunction "EN_8") (pintype "passive"))
      (node (ref "IC5") (pin "16") (pinfunction "VCC_16") (pintype "passive"))
      (node (ref "PS1") (pin "5") (pinfunction "OUT_5") (pintype "passive"))
      (node (ref "R1") (pin "2") (pinfunction "2_2") (pintype "passive"))
      (node (ref "R3") (pin "2") (pinfunction "2_2") (pintype "passive"))
      (node (ref "R4") (pin "2") (pinfunction "2_2") (pintype "passive"))
      (node (ref "R5") (pin "2") (pinfunction "2_2") (pintype "passive"))
      (node (ref "R8") (pin "2") (pinfunction "2_2") (pintype "passive"))
      (node (ref "S2") (pin "L2") (pinfunction "L2_L2") (pintype "passive"))
      (node (ref "S3") (pin "L2") (pinfunction "L2_L2") (pintype "passive"))
      (node (ref "S4") (pin "L2") (pinfunction "L2_L2") (pintype "passive"))
      (node (ref "S5") (pin "L2") (pinfunction "L2_L2") (pintype "passive"))
      (node (ref "S6") (pin "L2") (pinfunction "L2_L2") (pintype "passive"))
      (node (ref "S7") (pin "L2") (pinfunction "L2_L2") (pintype "passive"))
      (node (ref "S8") (pin "L2") (pinfunction "L2_L2") (pintype "passive"))
      (node (ref "S9") (pin "L2") (pinfunction "L2_L2") (pintype "passive"))
      (node (ref "TP1") (pin "1") (pinfunction "1_1") (pintype "passive"))
    )
    (net (code "53") (name "unconnected-(1-Pad6)") (class "Default")
      (node (ref "1") (pin "6") (pinfunction "6_6") (pintype "passive"))
    )
    (net (code "54") (name "unconnected-(1-Pad7)") (class "Default")
      (node (ref "1") (pin "7") (pinfunction "7_7") (pintype "passive"))
    )
    (net (code "55") (name "unconnected-(1-Pad8)") (class "Default")
      (node (ref "1") (pin "8") (pinfunction "8_8") (pintype "passive"))
    )
    (net (code "56") (name "unconnected-(1-Pad9)") (class "Default")
      (node (ref "1") (pin "9") (pinfunction "9_9") (pintype "passive"))
    )
    (net (code "57") (name "unconnected-(IC2-PA02-Pad18)") (class "Default")
      (node (ref "IC2") (pin "18") (pinfunction "PA02_18") (pintype "passive"))
    )
    (net (code "58") (name "unconnected-(IC2-PA03-Pad19)") (class "Default")
      (node (ref "IC2") (pin "19") (pinfunction "PA03_19") (pintype "passive"))
    )
    (net (code "59") (name "unconnected-(IC2-PA04-Pad20)") (class "Default")
      (node (ref "IC2") (pin "20") (pinfunction "PA04_20") (pintype "passive"))
    )
    (net (code "60") (name "unconnected-(IC2-PA05-Pad1)") (class "Default")
      (node (ref "IC2") (pin "1") (pinfunction "PA05_1") (pintype "passive"))
    )
    (net (code "61") (name "unconnected-(IC2-PA06-Pad2)") (class "Default")
      (node (ref "IC2") (pin "2") (pinfunction "PA06_2") (pintype "passive"))
    )
    (net (code "62") (name "unconnected-(IC2-PA07-Pad3)") (class "Default")
      (node (ref "IC2") (pin "3") (pinfunction "PA07_3") (pintype "passive"))
    )
    (net (code "63") (name "unconnected-(IC2-PA23-Pad10)") (class "Default")
      (node (ref "IC2") (pin "10") (pinfunction "PA23_10") (pintype "passive"))
    )
    (net (code "64") (name "unconnected-(IC3-NC-Pad11)") (class "Default")
      (node (ref "IC3") (pin "11") (pinfunction "NC_11") (pintype "passive"))
    )
    (net (code "65") (name "unconnected-(IC4-NC-Pad11)") (class "Default")
      (node (ref "IC4") (pin "11") (pinfunction "NC_11") (pintype "passive"))
    )
    (net (code "66") (name "unconnected-(PS1-NC-Pad4)") (class "Default")
      (node (ref "PS1") (pin "4") (pinfunction "NC_4") (pintype "passive"))
    )
    (net (code "67") (name "unconnected-(S1-Pad2)") (class "Default")
      (node (ref "S1") (pin "2") (pinfunction "2_2") (pintype "passive"))
    )
    (net (code "68") (name "unconnected-(S2-PadNC)") (class "Default")
      (node (ref "S2") (pin "NC") (pinfunction "NC_NC") (pintype "passive"))
    )
    (net (code "69") (name "unconnected-(S3-PadNC)") (class "Default")
      (node (ref "S3") (pin "NC") (pinfunction "NC_NC") (pintype "passive"))
    )
    (net (code "70") (name "unconnected-(S4-PadNC)") (class "Default")
      (node (ref "S4") (pin "NC") (pinfunction "NC_NC") (pintype "passive"))
    )
    (net (code "71") (name "unconnected-(S5-PadNC)") (class "Default")
      (node (ref "S5") (pin "NC") (pinfunction "NC_NC") (pintype "passive"))
    )
    (net (code "72") (name "unconnected-(S6-PadNC)") (class "Default")
      (node (ref "S6") (pin "NC") (pinfunction "NC_NC") (pintype "passive"))
    )
    (net (code "73") (name "unconnected-(S7-PadNC)") (class "Default")
      (node (ref "S7") (pin "NC") (pinfunction "NC_NC") (pintype "passive"))
    )
    (net (code "74") (name "unconnected-(S8-PadNC)") (class "Default")
      (node (ref "S8") (pin "NC") (pinfunction "NC_NC") (pintype "passive"))
    )
    (net (code "75") (name "unconnected-(S9-PadNC)") (class "Default")
      (node (ref "S9") (pin "NC") (pinfunction "NC_NC") (pintype "passive"))
    )
  )
)
